# mainboard_ESP32_WROOM.net
KiCad netlist of a schematic drawn in EAGLE
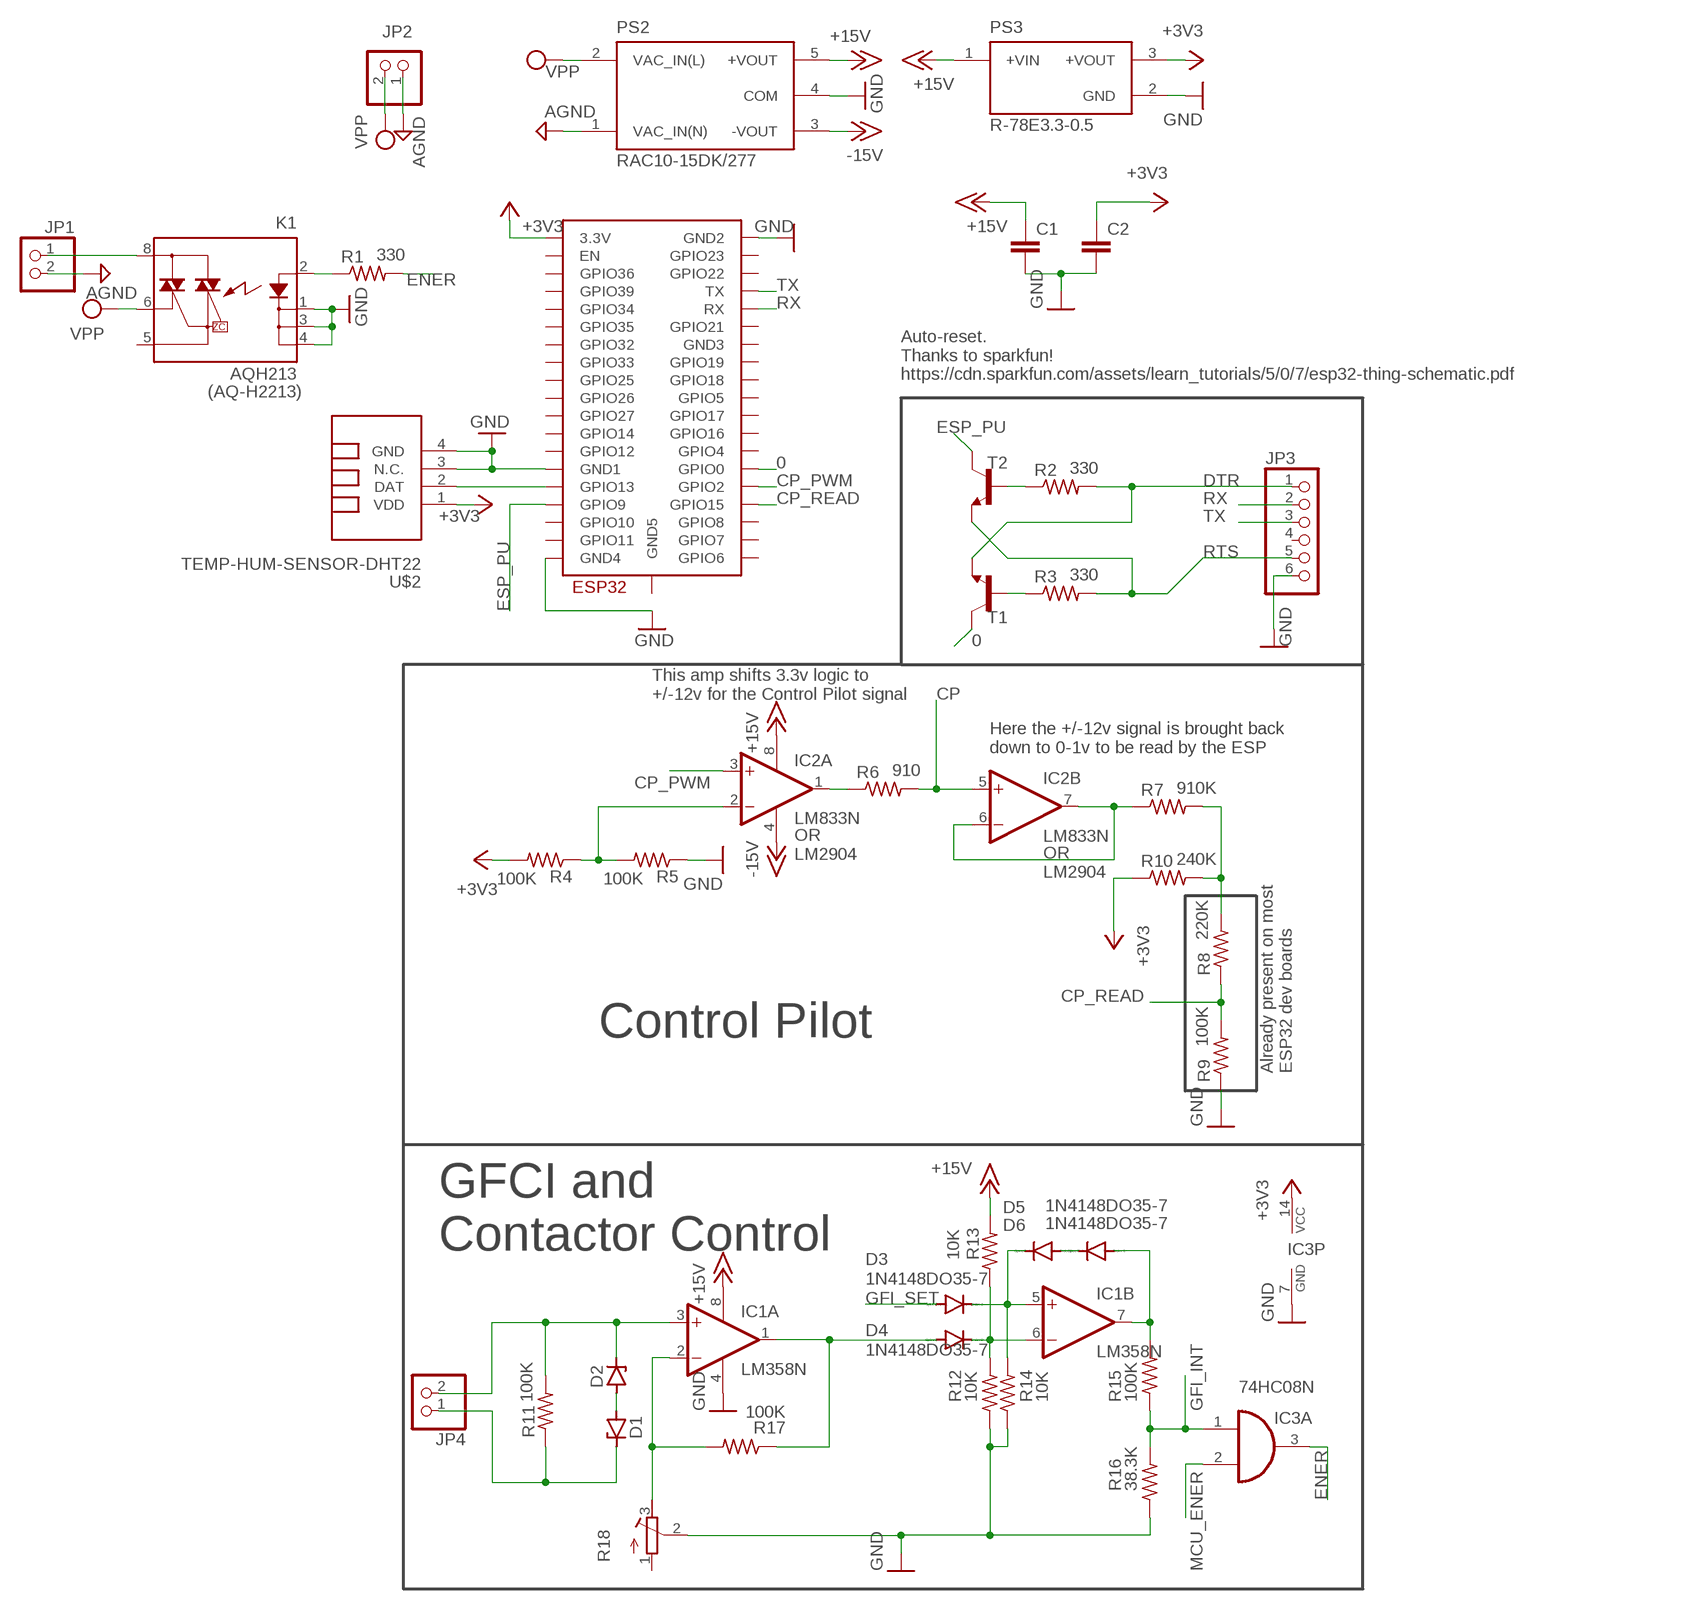
[diagram p0: schematic, sheet 1]

(export (version "E")
  (design (tool "Eeschema 10.0.6"))
  (components
    (comp (ref "C1")
      (value "C-EU025-025X050")
      (footprint "eagle-import:C025-025X050")
      (libsource (lib "eagle-import") (part "C-EU025-025X050"))
    )
    (comp (ref "C2")
      (value "C-EU025-025X050")
      (footprint "eagle-import:C025-025X050")
      (libsource (lib "eagle-import") (part "C-EU025-025X050"))
    )
    (comp (ref "D1")
      (value "ZENER-DIODEDO34-7")
      (footprint "eagle-import:DO34Z7")
      (libsource (lib "eagle-import") (part "ZENER-DIODEDO34-7"))
    )
    (comp (ref "D2")
      (value "ZENER-DIODEDO34-7")
      (footprint "eagle-import:DO34Z7")
      (libsource (lib "eagle-import") (part "ZENER-DIODEDO34-7"))
    )
    (comp (ref "D3")
      (value "1N4148DO35-7")
      (footprint "eagle-import:DO35-7")
      (libsource (lib "eagle-import") (part "1N4148DO35-7"))
    )
    (comp (ref "D4")
      (value "1N4148DO35-7")
      (footprint "eagle-import:DO35-7")
      (libsource (lib "eagle-import") (part "1N4148DO35-7"))
    )
    (comp (ref "D5")
      (value "1N4148DO35-7")
      (footprint "eagle-import:DO35-7")
      (libsource (lib "eagle-import") (part "1N4148DO35-7"))
    )
    (comp (ref "D6")
      (value "1N4148DO35-7")
      (footprint "eagle-import:DO35-7")
      (libsource (lib "eagle-import") (part "1N4148DO35-7"))
    )
    (comp (ref "IC1")
      (value "LM358N")
      (footprint "eagle-import:DIL08")
      (libsource (lib "eagle-import") (part "LM358N"))
    )
    (comp (ref "IC2")
      (value "LM833N")
      (footprint "eagle-import:DIL08")
      (libsource (lib "eagle-import") (part "LM833N"))
    )
    (comp (ref "IC3")
      (value "74HC08N")
      (footprint "eagle-import:DIL14")
      (libsource (lib "eagle-import") (part "7408NHC"))
    )
    (comp (ref "JP1")
      (value "PINHD-1X2")
      (footprint "eagle-import:1X02")
      (libsource (lib "eagle-import") (part "PINHD-1X2"))
    )
    (comp (ref "JP2")
      (value "PINHD-1X2")
      (footprint "eagle-import:1X02")
      (libsource (lib "eagle-import") (part "PINHD-1X2"))
    )
    (comp (ref "JP3")
      (value "PINHD-1X6")
      (footprint "eagle-import:1X06")
      (libsource (lib "eagle-import") (part "PINHD-1X6"))
    )
    (comp (ref "JP4")
      (value "PINHD-1X2")
      (footprint "eagle-import:1X02")
      (libsource (lib "eagle-import") (part "PINHD-1X2"))
    )
    (comp (ref "K1")
      (value "AQH213")
      (footprint "eagle-import:DIL07")
      (libsource (lib "eagle-import") (part "AQH213"))
    )
    (comp (ref "PS2")
      (value "RAC10-15DK/277")
      (footprint "eagle-import:CONV_RAC10-15DK_277")
      (fields (field (name "DIGI-KEY_PART_NUMBER") "945-3126-5-ND") (field (name "MF") "Recom Power"))
      (libsource (lib "eagle-import") (part "RAC10-15DK/277"))
    )
    (comp (ref "PS3")
      (value "R-78E3.3-0.5")
      (footprint "eagle-import:CONV_R-78E3.3-0.5")
      (fields (field (name "DIGI-KEY_PART_NUMBER") "945-1661-5-ND") (field (name "MF") "Recom Power"))
      (libsource (lib "eagle-import") (part "R-78E3.3-0.5"))
    )
    (comp (ref "R1")
      (value "330")
      (footprint "eagle-import:0204_7")
      (libsource (lib "eagle-import") (part "R-US_0204/7"))
    )
    (comp (ref "R2")
      (value "330")
      (footprint "eagle-import:0204_7")
      (libsource (lib "eagle-import") (part "R-US_0204/7"))
    )
    (comp (ref "R3")
      (value "330")
      (footprint "eagle-import:0204_7")
      (libsource (lib "eagle-import") (part "R-US_0204/7"))
    )
    (comp (ref "R4")
      (value "100K")
      (footprint "eagle-import:0204_7")
      (libsource (lib "eagle-import") (part "R-US_0204/7"))
    )
    (comp (ref "R5")
      (value "100K")
      (footprint "eagle-import:0204_7")
      (libsource (lib "eagle-import") (part "R-US_0204/7"))
    )
    (comp (ref "R6")
      (value "910")
      (footprint "eagle-import:0204_7")
      (libsource (lib "eagle-import") (part "R-US_0204/7"))
    )
    (comp (ref "R7")
      (value "910K")
      (footprint "eagle-import:0204_7")
      (libsource (lib "eagle-import") (part "R-US_0204/7"))
    )
    (comp (ref "R8")
      (value "220K")
      (footprint "eagle-import:0204_7")
      (libsource (lib "eagle-import") (part "R-US_0204/7"))
    )
    (comp (ref "R9")
      (value "100K")
      (footprint "eagle-import:0204_7")
      (libsource (lib "eagle-import") (part "R-US_0204/7"))
    )
    (comp (ref "R10")
      (value "240K")
      (footprint "eagle-import:0204_7")
      (libsource (lib "eagle-import") (part "R-US_0204/7"))
    )
    (comp (ref "R11")
      (value "100K")
      (footprint "eagle-import:0204_7")
      (libsource (lib "eagle-import") (part "R-US_0204/7"))
    )
    (comp (ref "R12")
      (value "10K")
      (footprint "eagle-import:0204_7")
      (libsource (lib "eagle-import") (part "R-US_0204/7"))
    )
    (comp (ref "R13")
      (value "10K")
      (footprint "eagle-import:0204_7")
      (libsource (lib "eagle-import") (part "R-US_0204/7"))
    )
    (comp (ref "R14")
      (value "10K")
      (footprint "eagle-import:0204_7")
      (libsource (lib "eagle-import") (part "R-US_0204/7"))
    )
    (comp (ref "R15")
      (value "100K")
      (footprint "eagle-import:0204_7")
      (libsource (lib "eagle-import") (part "R-US_0204/7"))
    )
    (comp (ref "R16")
      (value "38.3K")
      (footprint "eagle-import:0204_7")
      (libsource (lib "eagle-import") (part "R-US_0204/7"))
    )
    (comp (ref "R17")
      (value "100K")
      (footprint "eagle-import:0204_7")
      (libsource (lib "eagle-import") (part "R-US_0204/7"))
    )
    (comp (ref "R18")
      (value "R-TRIMM64W")
      (footprint "eagle-import:RTRIM64W")
      (libsource (lib "eagle-import") (part "R-TRIMM64W"))
    )
    (comp (ref "T1")
      (value "MMBT3904LT1-NPN-SOT23-BEC")
      (footprint "eagle-import:SOT23-BEC")
      (libsource (lib "eagle-import") (part "-NPN-SOT23-BECMMBT3904LT1"))
    )
    (comp (ref "T2")
      (value "MMBT3904LT1-NPN-SOT23-BEC")
      (footprint "eagle-import:SOT23-BEC")
      (libsource (lib "eagle-import") (part "-NPN-SOT23-BECMMBT3904LT1"))
    )
    (comp (ref "U$1")
      (value "ESP32-WROOM")
      (footprint "eagle-import:ESP32-WROOM")
      (libsource (lib "eagle-import") (part "ESP32-WROOM"))
    )
    (comp (ref "U$2")
      (value "TEMP-HUM-SENSOR-DHT22")
      (footprint "eagle-import:TEMP-HUM-SENSOR-DHT22")
      (libsource (lib "eagle-import") (part "TEMP-HUM-SENSOR-DHT22"))
    )
  )
  (nets
    (net (code "1") (name "+3V3") (class "Default")
      (node (ref "C2") (pin "1") (pinfunction "1_1") (pintype "passive"))
      (node (ref "IC3") (pin "14") (pinfunction "VCC_14") (pintype "power_in"))
      (node (ref "PS3") (pin "3") (pinfunction "+VOUT_3") (pintype "output"))
      (node (ref "R10") (pin "1") (pinfunction "1_1") (pintype "passive"))
      (node (ref "R4") (pin "2") (pinfunction "2_2") (pintype "passive"))
      (node (ref "U$1") (pin "3V3") (pinfunction "3.3V_3V3") (pintype "bidirectional"))
      (node (ref "U$2") (pin "1") (pinfunction "VDD_1") (pintype "power_in"))
    )
    (net (code "2") (name "+15V") (class "Default")
      (node (ref "C1") (pin "1") (pinfunction "1_1") (pintype "passive"))
      (node (ref "IC1") (pin "8") (pinfunction "V+_8") (pintype "power_in"))
      (node (ref "IC2") (pin "8") (pinfunction "V+_8") (pintype "power_in"))
      (node (ref "PS2") (pin "5") (pinfunction "+VOUT_5") (pintype "output"))
      (node (ref "PS3") (pin "1") (pinfunction "+VIN_1") (pintype "input"))
      (node (ref "R13") (pin "2") (pinfunction "2_2") (pintype "passive"))
    )
    (net (code "3") (name "-15V") (class "Default")
      (node (ref "IC2") (pin "4") (pinfunction "V-_4") (pintype "power_in"))
      (node (ref "PS2") (pin "3") (pinfunction "-VOUT_3") (pintype "output"))
    )
    (net (code "4") (name "/0") (class "Default")
      (node (ref "T1") (pin "C") (pinfunction "C_C") (pintype "passive"))
      (node (ref "U$1") (pin "IO0") (pinfunction "GPIO0_IO0") (pintype "bidirectional"))
    )
    (net (code "5") (name "/CP") (class "Default")
      (node (ref "IC2") (pin "5") (pinfunction "+IN_5") (pintype "input"))
      (node (ref "R6") (pin "2") (pinfunction "2_2") (pintype "passive"))
    )
    (net (code "6") (name "/CP_PWM") (class "Default")
      (node (ref "IC2") (pin "3") (pinfunction "+IN_3") (pintype "input"))
      (node (ref "U$1") (pin "IO2") (pinfunction "GPIO2_IO2") (pintype "bidirectional"))
    )
    (net (code "7") (name "/CP_READ") (class "Default")
      (node (ref "R8") (pin "1") (pinfunction "1_1") (pintype "passive"))
      (node (ref "R9") (pin "2") (pinfunction "2_2") (pintype "passive"))
      (node (ref "U$1") (pin "IO15") (pinfunction "GPIO15_IO15") (pintype "bidirectional"))
    )
    (net (code "8") (name "/DTR") (class "Default")
      (node (ref "JP3") (pin "1") (pinfunction "1_1") (pintype "passive"))
      (node (ref "R2") (pin "2") (pinfunction "2_2") (pintype "passive"))
      (node (ref "T1") (pin "E") (pinfunction "E_E") (pintype "passive"))
    )
    (net (code "9") (name "/ENER") (class "Default")
      (node (ref "IC3") (pin "3") (pinfunction "O_3") (pintype "output"))
      (node (ref "R1") (pin "2") (pinfunction "2_2") (pintype "passive"))
    )
    (net (code "10") (name "/ESP_PU") (class "Default")
      (node (ref "T2") (pin "C") (pinfunction "C_C") (pintype "passive"))
      (node (ref "U$1") (pin "SD2") (pinfunction "GPIO9_SD2") (pintype "bidirectional"))
    )
    (net (code "11") (name "/GFI_INT") (class "Default")
      (node (ref "IC3") (pin "1") (pinfunction "I0_1") (pintype "input"))
      (node (ref "R15") (pin "1") (pinfunction "1_1") (pintype "passive"))
      (node (ref "R16") (pin "2") (pinfunction "2_2") (pintype "passive"))
    )
    (net (code "12") (name "/GFI_SET") (class "Default")
      (node (ref "D3") (pin "A") (pinfunction "A_A") (pintype "passive"))
    )
    (net (code "13") (name "/MCU_ENER") (class "Default")
      (node (ref "IC3") (pin "2") (pinfunction "I1_2") (pintype "input"))
    )
    (net (code "14") (name "/RTS") (class "Default")
      (node (ref "JP3") (pin "5") (pinfunction "5_5") (pintype "passive"))
      (node (ref "R3") (pin "2") (pinfunction "2_2") (pintype "passive"))
      (node (ref "T2") (pin "E") (pinfunction "E_E") (pintype "passive"))
    )
    (net (code "15") (name "/RX") (class "Default")
      (node (ref "JP3") (pin "2") (pinfunction "2_2") (pintype "passive"))
      (node (ref "U$1") (pin "RX") (pinfunction "RX_RX") (pintype "bidirectional"))
    )
    (net (code "16") (name "/TX") (class "Default")
      (node (ref "JP3") (pin "3") (pinfunction "3_3") (pintype "passive"))
      (node (ref "U$1") (pin "TX") (pinfunction "TX_TX") (pintype "bidirectional"))
    )
    (net (code "17") (name "AGND") (class "Default")
      (node (ref "JP1") (pin "2") (pinfunction "2_2") (pintype "passive"))
      (node (ref "JP2") (pin "1") (pinfunction "1_1") (pintype "passive"))
      (node (ref "PS2") (pin "1") (pinfunction "VAC_IN(N)_1") (pintype "input"))
    )
    (net (code "18") (name "GND") (class "Default")
      (node (ref "C1") (pin "2") (pinfunction "2_2") (pintype "passive"))
      (node (ref "C2") (pin "2") (pinfunction "2_2") (pintype "passive"))
      (node (ref "IC1") (pin "4") (pinfunction "V-_4") (pintype "power_in"))
      (node (ref "IC3") (pin "7") (pinfunction "GND_7") (pintype "power_in"))
      (node (ref "JP3") (pin "6") (pinfunction "6_6") (pintype "passive"))
      (node (ref "K1") (pin "1") (pinfunction "K_1") (pintype "passive"))
      (node (ref "K1") (pin "3") (pinfunction "K1_3") (pintype "passive"))
      (node (ref "K1") (pin "4") (pinfunction "K2_4") (pintype "passive"))
      (node (ref "PS2") (pin "4") (pinfunction "COM_4") (pintype "power_in"))
      (node (ref "PS3") (pin "2") (pinfunction "GND_2") (pintype "power_in"))
      (node (ref "R12") (pin "1") (pinfunction "1_1") (pintype "passive"))
      (node (ref "R14") (pin "1") (pinfunction "1_1") (pintype "passive"))
      (node (ref "R16") (pin "1") (pinfunction "1_1") (pintype "passive"))
      (node (ref "R18") (pin "2") (pinfunction "S_2") (pintype "passive"))
      (node (ref "R5") (pin "1") (pinfunction "1_1") (pintype "passive"))
      (node (ref "R9") (pin "1") (pinfunction "1_1") (pintype "passive"))
      (node (ref "U$1") (pin "GND1") (pinfunction "GND1_GND1") (pintype "bidirectional"))
      (node (ref "U$1") (pin "GND2") (pinfunction "GND2_GND2") (pintype "bidirectional"))
      (node (ref "U$1") (pin "GND4") (pinfunction "GND4_GND4") (pintype "bidirectional"))
      (node (ref "U$2") (pin "3") (pinfunction "N.C._3") (pintype "passive"))
      (node (ref "U$2") (pin "4") (pinfunction "GND_4") (pintype "power_in"))
    )
    (net (code "19") (name "Net-(D1-PadA)") (class "Default")
      (node (ref "D1") (pin "A") (pinfunction "A_A") (pintype "passive"))
      (node (ref "D2") (pin "A") (pinfunction "A_A") (pintype "passive"))
    )
    (net (code "20") (name "Net-(D1-PadC)") (class "Default")
      (node (ref "D1") (pin "C") (pinfunction "C_C") (pintype "passive"))
      (node (ref "JP4") (pin "1") (pinfunction "1_1") (pintype "passive"))
      (node (ref "R11") (pin "1") (pinfunction "1_1") (pintype "passive"))
    )
    (net (code "21") (name "Net-(D5-PadA)") (class "Default")
      (node (ref "D5") (pin "A") (pinfunction "A_A") (pintype "passive"))
      (node (ref "D6") (pin "C") (pinfunction "C_C") (pintype "passive"))
    )
    (net (code "22") (name "Net-(IC1A-+IN)") (class "Default")
      (node (ref "D2") (pin "C") (pinfunction "C_C") (pintype "passive"))
      (node (ref "IC1") (pin "3") (pinfunction "+IN_3") (pintype "input"))
      (node (ref "JP4") (pin "2") (pinfunction "2_2") (pintype "passive"))
      (node (ref "R11") (pin "2") (pinfunction "2_2") (pintype "passive"))
    )
    (net (code "23") (name "Net-(IC1A--IN)") (class "Default")
      (node (ref "IC1") (pin "2") (pinfunction "-IN_2") (pintype "input"))
      (node (ref "R17") (pin "2") (pinfunction "2_2") (pintype "passive"))
      (node (ref "R18") (pin "3") (pinfunction "E_3") (pintype "passive"))
    )
    (net (code "24") (name "Net-(IC1A-OUT)") (class "Default")
      (node (ref "D4") (pin "A") (pinfunction "A_A") (pintype "passive"))
      (node (ref "IC1") (pin "1") (pinfunction "OUT_1") (pintype "output"))
      (node (ref "R17") (pin "1") (pinfunction "1_1") (pintype "passive"))
    )
    (net (code "25") (name "Net-(IC1B-+IN)") (class "Default")
      (node (ref "D3") (pin "C") (pinfunction "C_C") (pintype "passive"))
      (node (ref "D5") (pin "C") (pinfunction "C_C") (pintype "passive"))
      (node (ref "IC1") (pin "5") (pinfunction "+IN_5") (pintype "input"))
      (node (ref "R14") (pin "2") (pinfunction "2_2") (pintype "passive"))
    )
    (net (code "26") (name "Net-(IC1B--IN)") (class "Default")
      (node (ref "D4") (pin "C") (pinfunction "C_C") (pintype "passive"))
      (node (ref "IC1") (pin "6") (pinfunction "-IN_6") (pintype "input"))
      (node (ref "R12") (pin "2") (pinfunction "2_2") (pintype "passive"))
      (node (ref "R13") (pin "1") (pinfunction "1_1") (pintype "passive"))
    )
    (net (code "27") (name "Net-(IC1B-OUT)") (class "Default")
      (node (ref "D6") (pin "A") (pinfunction "A_A") (pintype "passive"))
      (node (ref "IC1") (pin "7") (pinfunction "OUT_7") (pintype "output"))
      (node (ref "R15") (pin "2") (pinfunction "2_2") (pintype "passive"))
    )
    (net (code "28") (name "Net-(IC2A--IN)") (class "Default")
      (node (ref "IC2") (pin "2") (pinfunction "-IN_2") (pintype "input"))
      (node (ref "R4") (pin "1") (pinfunction "1_1") (pintype "passive"))
      (node (ref "R5") (pin "2") (pinfunction "2_2") (pintype "passive"))
    )
    (net (code "29") (name "Net-(IC2A-OUT)") (class "Default")
      (node (ref "IC2") (pin "1") (pinfunction "OUT_1") (pintype "output"))
      (node (ref "R6") (pin "1") (pinfunction "1_1") (pintype "passive"))
    )
    (net (code "30") (name "Net-(IC2B--IN)") (class "Default")
      (node (ref "IC2") (pin "6") (pinfunction "-IN_6") (pintype "input"))
      (node (ref "IC2") (pin "7") (pinfunction "OUT_7") (pintype "output"))
      (node (ref "R7") (pin "1") (pinfunction "1_1") (pintype "passive"))
    )
    (net (code "31") (name "Net-(K1-A)") (class "Default")
      (node (ref "K1") (pin "2") (pinfunction "A_2") (pintype "passive"))
      (node (ref "R1") (pin "1") (pinfunction "1_1") (pintype "passive"))
    )
    (net (code "32") (name "Net-(K1-DS1)") (class "Default")
      (node (ref "JP1") (pin "1") (pinfunction "1_1") (pintype "passive"))
      (node (ref "K1") (pin "8") (pinfunction "DS1_8") (pintype "passive"))
    )
    (net (code "33") (name "Net-(R2-Pad1)") (class "Default")
      (node (ref "R2") (pin "1") (pinfunction "1_1") (pintype "passive"))
      (node (ref "T2") (pin "B") (pinfunction "B_B") (pintype "passive"))
    )
    (net (code "34") (name "Net-(R3-Pad1)") (class "Default")
      (node (ref "R3") (pin "1") (pinfunction "1_1") (pintype "passive"))
      (node (ref "T1") (pin "B") (pinfunction "B_B") (pintype "passive"))
    )
    (net (code "35") (name "Net-(R10-Pad2)") (class "Default")
      (node (ref "R10") (pin "2") (pinfunction "2_2") (pintype "passive"))
      (node (ref "R7") (pin "2") (pinfunction "2_2") (pintype "passive"))
      (node (ref "R8") (pin "2") (pinfunction "2_2") (pintype "passive"))
    )
    (net (code "36") (name "Net-(U$1-GPIO13)") (class "Default")
      (node (ref "U$1") (pin "IO13") (pinfunction "GPIO13_IO13") (pintype "bidirectional"))
      (node (ref "U$2") (pin "2") (pinfunction "DAT_2") (pintype "bidirectional"))
    )
    (net (code "37") (name "VPP") (class "Default")
      (node (ref "JP2") (pin "2") (pinfunction "2_2") (pintype "passive"))
      (node (ref "K1") (pin "6") (pinfunction "DS3_6") (pintype "passive"))
      (node (ref "PS2") (pin "2") (pinfunction "VAC_IN(L)_2") (pintype "input"))
    )
    (net (code "38") (name "unconnected-(JP3-Pad4)") (class "Default")
      (node (ref "JP3") (pin "4") (pinfunction "4_4") (pintype "passive"))
    )
    (net (code "39") (name "unconnected-(K1-DS2-Pad5)") (class "Default")
      (node (ref "K1") (pin "5") (pinfunction "DS2_5") (pintype "passive"))
    )
    (net (code "40") (name "unconnected-(R18-A-Pad1)") (class "Default")
      (node (ref "R18") (pin "1") (pinfunction "A_1") (pintype "passive"))
    )
    (net (code "41") (name "unconnected-(U$1-GPIO4-PadIO4)") (class "Default")
      (node (ref "U$1") (pin "IO4") (pinfunction "GPIO4_IO4") (pintype "bidirectional"))
    )
    (net (code "42") (name "unconnected-(U$1-GPIO5-PadIO5)") (class "Default")
      (node (ref "U$1") (pin "IO5") (pinfunction "GPIO5_IO5") (pintype "bidirectional"))
    )
    (net (code "43") (name "unconnected-(U$1-GPIO6-PadCLK)") (class "Default")
      (node (ref "U$1") (pin "CLK") (pinfunction "GPIO6_CLK") (pintype "bidirectional"))
    )
    (net (code "44") (name "unconnected-(U$1-GPIO7-PadSD0)") (class "Default")
      (node (ref "U$1") (pin "SD0") (pinfunction "GPIO7_SD0") (pintype "bidirectional"))
    )
    (net (code "45") (name "unconnected-(U$1-GPIO8-PadSD1)") (class "Default")
      (node (ref "U$1") (pin "SD1") (pinfunction "GPIO8_SD1") (pintype "bidirectional"))
    )
    (net (code "46") (name "unconnected-(U$1-GPIO10-PadSD3)") (class "Default")
      (node (ref "U$1") (pin "SD3") (pinfunction "GPIO10_SD3") (pintype "bidirectional"))
    )
    (net (code "47") (name "unconnected-(U$1-GPIO11-PadCMD)") (class "Default")
      (node (ref "U$1") (pin "CMD") (pinfunction "GPIO11_CMD") (pintype "bidirectional"))
    )
    (net (code "48") (name "unconnected-(U$1-GPIO12-PadIO12)") (class "Default")
      (node (ref "U$1") (pin "IO12") (pinfunction "GPIO12_IO12") (pintype "bidirectional"))
    )
    (net (code "49") (name "unconnected-(U$1-GPIO14-PadIO14)") (class "Default")
      (node (ref "U$1") (pin "IO14") (pinfunction "GPIO14_IO14") (pintype "bidirectional"))
    )
    (net (code "50") (name "unconnected-(U$1-GPIO16-PadIO16)") (class "Default")
      (node (ref "U$1") (pin "IO16") (pinfunction "GPIO16_IO16") (pintype "bidirectional"))
    )
    (net (code "51") (name "unconnected-(U$1-GPIO17-PadIO17)") (class "Default")
      (node (ref "U$1") (pin "IO17") (pinfunction "GPIO17_IO17") (pintype "bidirectional"))
    )
    (net (code "52") (name "unconnected-(U$1-GPIO18-PadIO18)") (class "Default")
      (node (ref "U$1") (pin "IO18") (pinfunction "GPIO18_IO18") (pintype "bidirectional"))
    )
    (net (code "53") (name "unconnected-(U$1-GPIO19-PadIO19)") (class "Default")
      (node (ref "U$1") (pin "IO19") (pinfunction "GPIO19_IO19") (pintype "bidirectional"))
    )
    (net (code "54") (name "unconnected-(U$1-GPIO21-PadIO21)") (class "Default")
      (node (ref "U$1") (pin "IO21") (pinfunction "GPIO21_IO21") (pintype "bidirectional"))
    )
    (net (code "55") (name "unconnected-(U$1-GPIO22-PadIO22)") (class "Default")
      (node (ref "U$1") (pin "IO22") (pinfunction "GPIO22_IO22") (pintype "bidirectional"))
    )
    (net (code "56") (name "unconnected-(U$1-GPIO23-PadIO23)") (class "Default")
      (node (ref "U$1") (pin "IO23") (pinfunction "GPIO23_IO23") (pintype "bidirectional"))
    )
    (net (code "57") (name "unconnected-(U$1-GPIO25-PadIO25)") (class "Default")
      (node (ref "U$1") (pin "IO25") (pinfunction "GPIO25_IO25") (pintype "bidirectional"))
    )
    (net (code "58") (name "unconnected-(U$1-GPIO26-PadIO26)") (class "Default")
      (node (ref "U$1") (pin "IO26") (pinfunction "GPIO26_IO26") (pintype "bidirectional"))
    )
    (net (code "59") (name "unconnected-(U$1-GPIO27-PadIO27)") (class "Default")
      (node (ref "U$1") (pin "IO27") (pinfunction "GPIO27_IO27") (pintype "bidirectional"))
    )
    (net (code "60") (name "unconnected-(U$1-GPIO32-PadIO32)") (class "Default")
      (node (ref "U$1") (pin "IO32") (pinfunction "GPIO32_IO32") (pintype "bidirectional"))
    )
    (net (code "61") (name "unconnected-(U$1-GPIO33-PadIO33)") (class "Default")
      (node (ref "U$1") (pin "IO33") (pinfunction "GPIO33_IO33") (pintype "bidirectional"))
    )
    (net (code "62") (name "unconnected-(U$1-GPIO34-PadIO34)") (class "Default")
      (node (ref "U$1") (pin "IO34") (pinfunction "GPIO34_IO34") (pintype "bidirectional"))
    )
    (net (code "63") (name "unconnected-(U$1-GPIO35-PadIO35)") (class "Default")
      (node (ref "U$1") (pin "IO35") (pinfunction "GPIO35_IO35") (pintype "bidirectional"))
    )
    (net (code "64") (name "unconnected-(U$1-GPIO36-PadSENSOR_VP)") (class "Default")
      (node (ref "U$1") (pin "SENSOR_VP") (pinfunction "GPIO36_SENSOR_VP") (pintype "bidirectional"))
    )
    (net (code "65") (name "unconnected-(U$1-GPIO39-PadSENSOR_VN)") (class "Default")
      (node (ref "U$1") (pin "SENSOR_VN") (pinfunction "GPIO39_SENSOR_VN") (pintype "bidirectional"))
    )
    (net (code "66") (name "unconnected-(U$1-PadEN)") (class "Default")
      (node (ref "U$1") (pin "EN") (pinfunction "EN_EN") (pintype "bidirectional"))
    )
    (net (code "67") (name "unconnected-(U$1-PadGND3)") (class "Default")
      (node (ref "U$1") (pin "GND3") (pinfunction "GND3_GND3") (pintype "bidirectional"))
    )
    (net (code "68") (name "unconnected-(U$1-PadGND5)") (class "Default")
      (node (ref "U$1") (pin "GND5") (pinfunction "GND5_GND5") (pintype "bidirectional"))
    )
  )
)
